# Driver.net
KiCad netlist of a schematic drawn in EAGLE
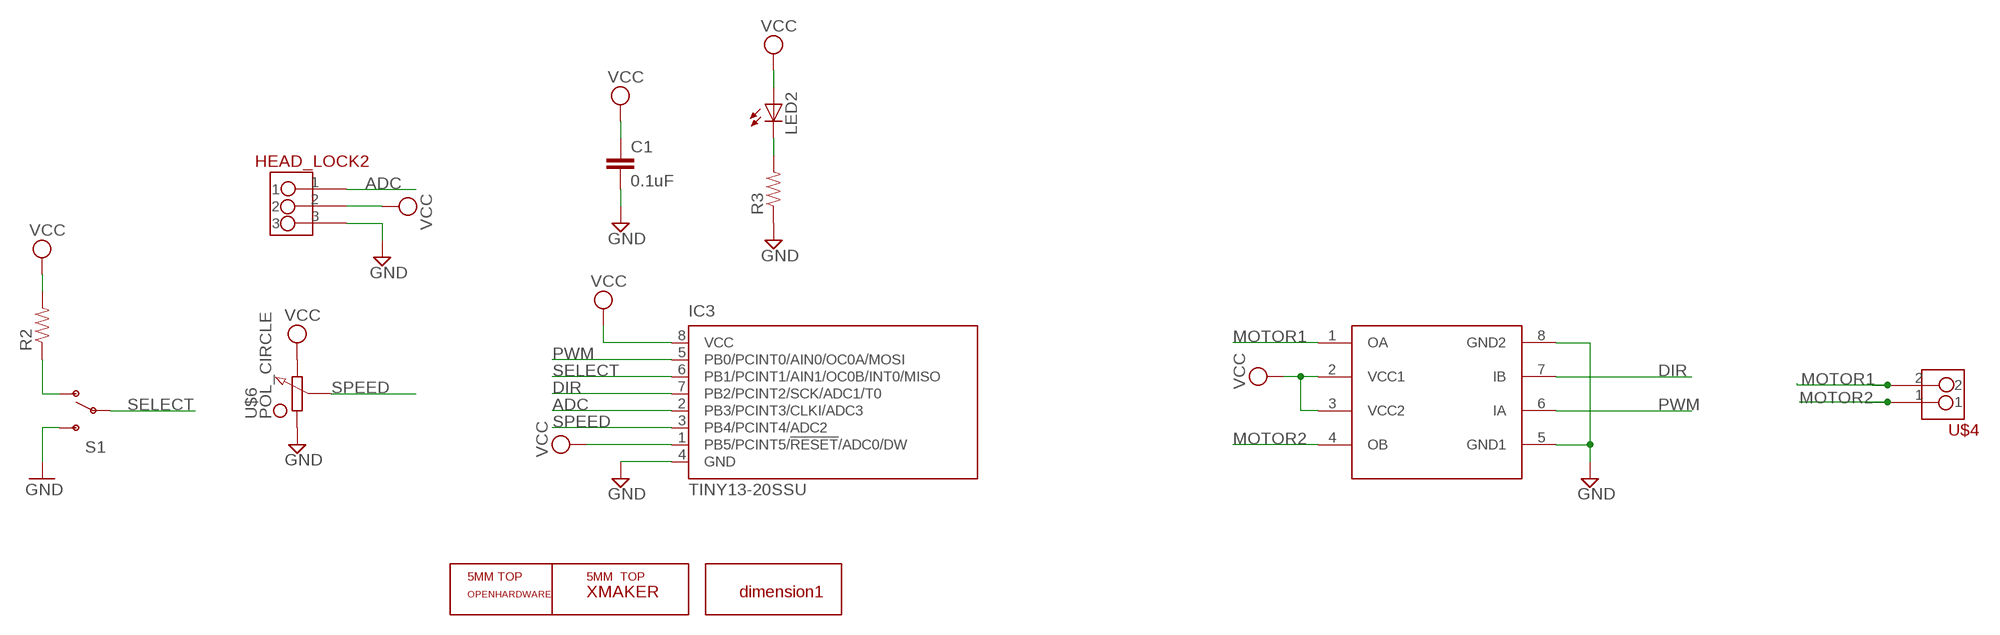
[diagram p0: schematic, sheet 1]

(export (version "E")
  (design (tool "Eeschema 10.0.6"))
  (components
    (comp (ref "C1")
      (value "0.1uF")
      (footprint "eagle-import:0603-CAP")
      (libsource (lib "eagle-import") (part "CAP0603-CAP"))
    )
    (comp (ref "HEAD_LOCK2")
      (value "HEAD_LOCK")
      (footprint "eagle-import:HEAD_LOCK")
      (libsource (lib "eagle-import") (part "HEAD_LOCK"))
    )
    (comp (ref "IC3")
      (value "TINY13-20SSU")
      (footprint "eagle-import:8S1")
      (fields (field (name "MPN") "ATTINY13-20SSU"))
      (libsource (lib "eagle-import") (part "TINY13SSU-20"))
    )
    (comp (ref "LED2")
      (value "LED_ESML0603")
      (footprint "eagle-import:LED_SML0603")
      (libsource (lib "eagle-import") (part "LED_ESML0603"))
    )
    (comp (ref "R2")
      (value "RESISTOR0603-RES")
      (footprint "eagle-import:0603-RES")
      (libsource (lib "eagle-import") (part "RESISTOR0603-RES"))
    )
    (comp (ref "R3")
      (value "0.27OHM-1/10W-1%(0603)")
      (footprint "eagle-import:0603-RES")
      (libsource (lib "eagle-import") (part "0.27OHM-1/10W-1%(0603)"))
    )
    (comp (ref "S1")
      (value "SWITCH-SPDTKIT")
      (footprint "eagle-import:SWITCH-SPDT_KIT")
      (libsource (lib "eagle-import") (part "SWITCH-SPDTKIT"))
    )
    (comp (ref "U$1")
      (value "DIMENSION1")
      (footprint "eagle-import:DIMENSION1")
      (libsource (lib "eagle-import") (part "DIMENSION1"))
    )
    (comp (ref "U$2")
      (value "L9110")
      (footprint "eagle-import:SOP8")
      (libsource (lib "eagle-import") (part "L9110"))
    )
    (comp (ref "U$4")
      (value "HEAD_LOCK2")
      (footprint "eagle-import:HEAD_LOCK2")
      (libsource (lib "eagle-import") (part "HEAD_LOCK2"))
    )
    (comp (ref "U$6")
      (value "POL_CIRCLE")
      (footprint "eagle-import:POT_CIRCLE")
      (libsource (lib "eagle-import") (part "POL_CIRCLE"))
    )
    (comp (ref "U$7")
      (value "XMAKERLOGO_5MM_TOP")
      (footprint "eagle-import:XMAKERLOGO_5MM_TOP")
      (libsource (lib "eagle-import") (part "XMAKERLOGO_5MM_TOP"))
    )
    (comp (ref "U$8")
      (value "OPENHARDWARE_5MM_TOP")
      (footprint "eagle-import:OPENSOURCE_5MM_TOP")
      (libsource (lib "eagle-import") (part "OPENHARDWARE_5MM_TOP"))
    )
  )
  (nets
    (net (code "1") (name "/ADC") (class "Default")
      (node (ref "HEAD_LOCK2") (pin "1") (pinfunction "1_1") (pintype "passive"))
      (node (ref "IC3") (pin "2") (pinfunction "PB3/PCINT3/CLKI/ADC3_2") (pintype "bidirectional"))
    )
    (net (code "2") (name "/DIR") (class "Default")
      (node (ref "IC3") (pin "7") (pinfunction "PB2/PCINT2/SCK/ADC1/T0_7") (pintype "bidirectional"))
      (node (ref "U$2") (pin "7") (pinfunction "IB_7") (pintype "bidirectional"))
    )
    (net (code "3") (name "/MOTOR1") (class "Default")
      (node (ref "U$2") (pin "1") (pinfunction "OA_1") (pintype "bidirectional"))
      (node (ref "U$4") (pin "2") (pinfunction "2_2") (pintype "passive"))
    )
    (net (code "4") (name "/MOTOR2") (class "Default")
      (node (ref "U$2") (pin "4") (pinfunction "OB_4") (pintype "bidirectional"))
      (node (ref "U$4") (pin "1") (pinfunction "1_1") (pintype "passive"))
    )
    (net (code "5") (name "/PWM") (class "Default")
      (node (ref "IC3") (pin "5") (pinfunction "PB0/PCINT0/AIN0/OC0A/MOSI_5") (pintype "bidirectional"))
      (node (ref "U$2") (pin "6") (pinfunction "IA_6") (pintype "bidirectional"))
    )
    (net (code "6") (name "/SELECT") (class "Default")
      (node (ref "IC3") (pin "6") (pinfunction "PB1/PCINT1/AIN1/OC0B/INT0/MISO_6") (pintype "bidirectional"))
      (node (ref "S1") (pin "2") (pinfunction "P_2") (pintype "passive"))
    )
    (net (code "7") (name "/SPEED") (class "Default")
      (node (ref "IC3") (pin "3") (pinfunction "PB4/PCINT4/ADC2_3") (pintype "bidirectional"))
      (node (ref "U$6") (pin "P$2") (pinfunction "2_P$2") (pintype "passive"))
    )
    (net (code "8") (name "GND") (class "Default")
      (node (ref "C1") (pin "2") (pinfunction "2_2") (pintype "passive"))
      (node (ref "HEAD_LOCK2") (pin "3") (pinfunction "3_3") (pintype "passive"))
      (node (ref "IC3") (pin "4") (pinfunction "GND_4") (pintype "power_in"))
      (node (ref "R3") (pin "1") (pinfunction "1_1") (pintype "passive"))
      (node (ref "S1") (pin "3") (pinfunction "S_3") (pintype "passive"))
      (node (ref "U$2") (pin "5") (pinfunction "GND1_5") (pintype "bidirectional"))
      (node (ref "U$2") (pin "8") (pinfunction "GND2_8") (pintype "bidirectional"))
      (node (ref "U$6") (pin "P$3") (pinfunction "3_P$3") (pintype "passive"))
    )
    (net (code "9") (name "Net-(LED2-PadC)") (class "Default")
      (node (ref "LED2") (pin "C") (pinfunction "C_C") (pintype "passive"))
      (node (ref "R3") (pin "2") (pinfunction "2_2") (pintype "passive"))
    )
    (net (code "10") (name "Net-(S1-O)") (class "Default")
      (node (ref "R2") (pin "1") (pinfunction "1_1") (pintype "passive"))
      (node (ref "S1") (pin "1") (pinfunction "O_1") (pintype "passive"))
    )
    (net (code "11") (name "VCC") (class "Default")
      (node (ref "C1") (pin "1") (pinfunction "1_1") (pintype "passive"))
      (node (ref "HEAD_LOCK2") (pin "2") (pinfunction "2_2") (pintype "passive"))
      (node (ref "IC3") (pin "1") (pinfunction "PB5/PCINT5/~{RESET}/ADC0/DW_1") (pintype "bidirectional"))
      (node (ref "IC3") (pin "8") (pinfunction "VCC_8") (pintype "power_in"))
      (node (ref "LED2") (pin "A") (pinfunction "A_A") (pintype "passive"))
      (node (ref "R2") (pin "2") (pinfunction "2_2") (pintype "passive"))
      (node (ref "U$2") (pin "2") (pinfunction "VCC1_2") (pintype "bidirectional"))
      (node (ref "U$2") (pin "3") (pinfunction "VCC2_3") (pintype "bidirectional"))
      (node (ref "U$6") (pin "P$1") (pinfunction "1_P$1") (pintype "passive"))
    )
  )
)
